# v1_2.net
KiCad netlist of a schematic drawn in EAGLE
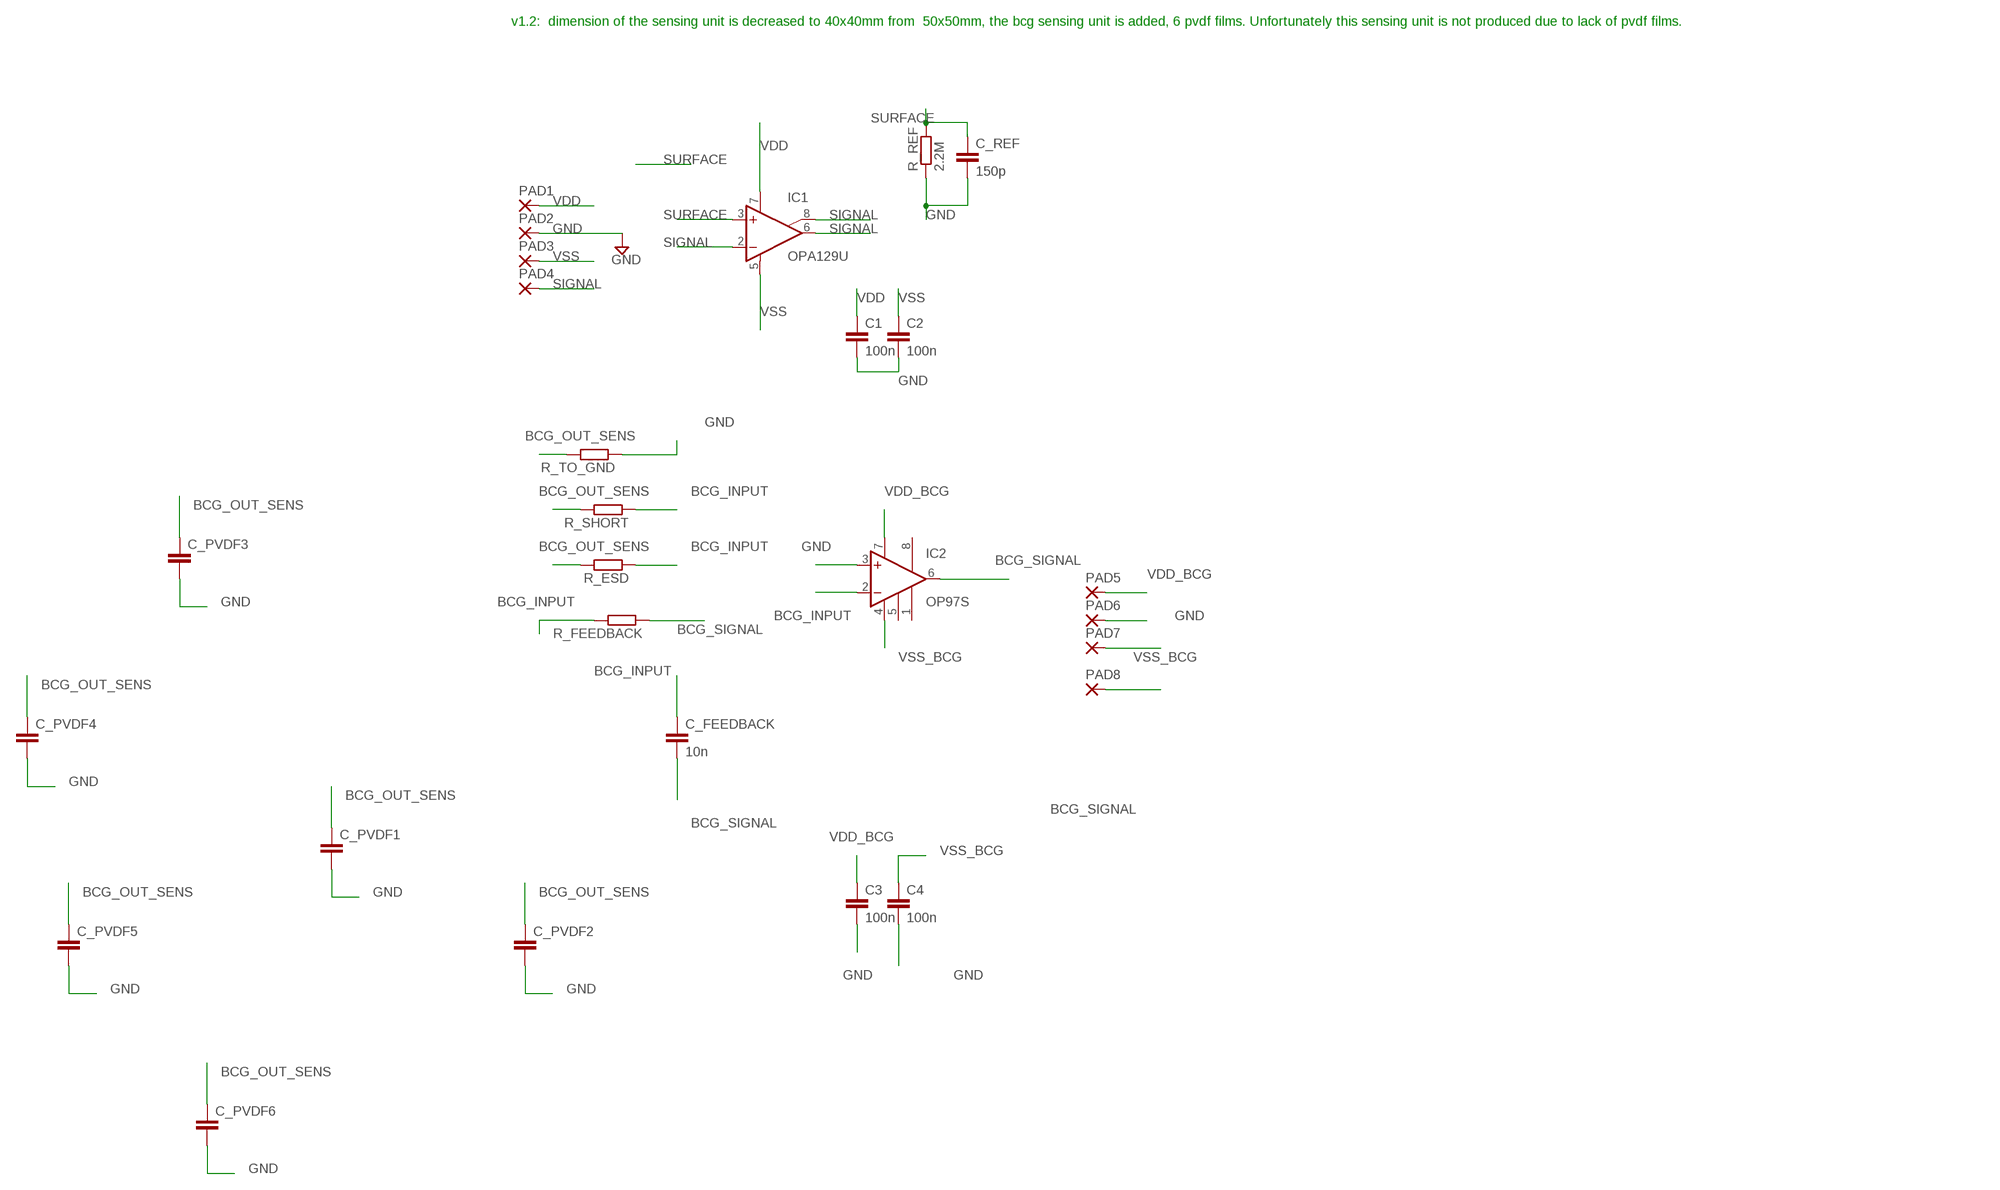
[diagram p0: schematic, sheet 1]

(export (version "E")
  (design (tool "Eeschema 10.0.6"))
  (components
    (comp (ref "C1")
      (value "100n")
      (footprint "eagle-import:C0805")
      (libsource (lib "eagle-import") (part "resistor_C-EUC0805"))
    )
    (comp (ref "C2")
      (value "100n")
      (footprint "eagle-import:C0805")
      (libsource (lib "eagle-import") (part "resistor_C-EUC0805"))
    )
    (comp (ref "C3")
      (value "100n")
      (footprint "eagle-import:C0805")
      (libsource (lib "eagle-import") (part "resistor_C-EUC0805"))
    )
    (comp (ref "C4")
      (value "100n")
      (footprint "eagle-import:C0805")
      (libsource (lib "eagle-import") (part "resistor_C-EUC0805"))
    )
    (comp (ref "C_FEEDBACK")
      (value "10n")
      (footprint "eagle-import:C0805")
      (libsource (lib "eagle-import") (part "C-EUC0805"))
    )
    (comp (ref "C_PVDF1")
      (value "C-EUC0805")
      (footprint "eagle-import:C0805")
      (libsource (lib "eagle-import") (part "C-EUC0805"))
    )
    (comp (ref "C_PVDF2")
      (value "C-EUC0805")
      (footprint "eagle-import:C0805")
      (libsource (lib "eagle-import") (part "C-EUC0805"))
    )
    (comp (ref "C_PVDF3")
      (value "C-EUC0805")
      (footprint "eagle-import:C0805")
      (libsource (lib "eagle-import") (part "C-EUC0805"))
    )
    (comp (ref "C_PVDF4")
      (value "C-EUC0805")
      (footprint "eagle-import:C0805")
      (libsource (lib "eagle-import") (part "C-EUC0805"))
    )
    (comp (ref "C_PVDF5")
      (value "C-EUC0805")
      (footprint "eagle-import:C0805")
      (libsource (lib "eagle-import") (part "C-EUC0805"))
    )
    (comp (ref "C_PVDF6")
      (value "C-EUC0805")
      (footprint "eagle-import:C0805")
      (libsource (lib "eagle-import") (part "C-EUC0805"))
    )
    (comp (ref "C_REF")
      (value "150p")
      (footprint "eagle-import:C0805")
      (libsource (lib "eagle-import") (part "resistor_C-EUC0805"))
    )
    (comp (ref "IC1")
      (value "OPA129U")
      (footprint "eagle-import:SO08")
      (fields (field (name "MF") "TEXAS INSTRUMENTS"))
      (libsource (lib "eagle-import") (part "OPA129U"))
    )
    (comp (ref "IC2")
      (value "OP97S")
      (footprint "eagle-import:SO08")
      (libsource (lib "eagle-import") (part "OP97S"))
    )
    (comp (ref "PAD1")
      (value "SMD5")
      (footprint "eagle-import:SMD2,54-5,08")
      (libsource (lib "eagle-import") (part "SMD5"))
    )
    (comp (ref "PAD2")
      (value "SMD5")
      (footprint "eagle-import:SMD2,54-5,08")
      (libsource (lib "eagle-import") (part "SMD5"))
    )
    (comp (ref "PAD3")
      (value "SMD5")
      (footprint "eagle-import:SMD2,54-5,08")
      (libsource (lib "eagle-import") (part "SMD5"))
    )
    (comp (ref "PAD4")
      (value "SMD5")
      (footprint "eagle-import:SMD2,54-5,08")
      (libsource (lib "eagle-import") (part "SMD5"))
    )
    (comp (ref "PAD5")
      (value "SMD5")
      (footprint "eagle-import:SMD2,54-5,08")
      (libsource (lib "eagle-import") (part "SMD5"))
    )
    (comp (ref "PAD6")
      (value "SMD5")
      (footprint "eagle-import:SMD2,54-5,08")
      (libsource (lib "eagle-import") (part "SMD5"))
    )
    (comp (ref "PAD7")
      (value "SMD5")
      (footprint "eagle-import:SMD2,54-5,08")
      (libsource (lib "eagle-import") (part "SMD5"))
    )
    (comp (ref "PAD8")
      (value "SMD5")
      (footprint "eagle-import:SMD2,54-5,08")
      (libsource (lib "eagle-import") (part "wirepad_412_SMD5"))
    )
    (comp (ref "R_ESD")
      (value "1M")
      (footprint "eagle-import:M0805")
      (libsource (lib "eagle-import") (part "rcl_334_R-EU_M0805"))
    )
    (comp (ref "R_FEEDBACK")
      (value "100M")
      (footprint "eagle-import:M0805")
      (libsource (lib "eagle-import") (part "rcl_334_R-EU_M0805"))
    )
    (comp (ref "R_REF")
      (value "2.2M")
      (footprint "eagle-import:M0805")
      (libsource (lib "eagle-import") (part "R-EU_M0805"))
    )
    (comp (ref "R_SHORT")
      (value "1M")
      (footprint "eagle-import:M0805")
      (libsource (lib "eagle-import") (part "rcl_334_R-EU_M0805"))
    )
    (comp (ref "R_TO_GND")
      (value "1M")
      (footprint "eagle-import:M0805")
      (libsource (lib "eagle-import") (part "rcl_334_R-EU_M0805"))
    )
  )
  (nets
    (net (code "1") (name "/BCG_INPUT") (class "Default")
      (node (ref "C_FEEDBACK") (pin "1") (pinfunction "1_1") (pintype "passive"))
      (node (ref "IC2") (pin "2") (pinfunction "-IN_2") (pintype "input"))
      (node (ref "R_ESD") (pin "1") (pinfunction "1_1") (pintype "passive"))
      (node (ref "R_FEEDBACK") (pin "2") (pinfunction "2_2") (pintype "passive"))
      (node (ref "R_SHORT") (pin "1") (pinfunction "1_1") (pintype "passive"))
    )
    (net (code "2") (name "/BCG_OUT_SENS") (class "Default")
      (node (ref "C_PVDF1") (pin "1") (pinfunction "1_1") (pintype "passive"))
      (node (ref "C_PVDF2") (pin "1") (pinfunction "1_1") (pintype "passive"))
      (node (ref "C_PVDF3") (pin "1") (pinfunction "1_1") (pintype "passive"))
      (node (ref "C_PVDF4") (pin "1") (pinfunction "1_1") (pintype "passive"))
      (node (ref "C_PVDF5") (pin "1") (pinfunction "1_1") (pintype "passive"))
      (node (ref "C_PVDF6") (pin "1") (pinfunction "1_1") (pintype "passive"))
      (node (ref "R_ESD") (pin "2") (pinfunction "2_2") (pintype "passive"))
      (node (ref "R_SHORT") (pin "2") (pinfunction "2_2") (pintype "passive"))
      (node (ref "R_TO_GND") (pin "2") (pinfunction "2_2") (pintype "passive"))
    )
    (net (code "3") (name "/BCG_SIGNAL") (class "Default")
      (node (ref "C_FEEDBACK") (pin "2") (pinfunction "2_2") (pintype "passive"))
      (node (ref "IC2") (pin "6") (pinfunction "OUT_6") (pintype "output"))
      (node (ref "PAD8") (pin "1") (pinfunction "P_1") (pintype "passive"))
      (node (ref "R_FEEDBACK") (pin "1") (pinfunction "1_1") (pintype "passive"))
    )
    (net (code "4") (name "/SIGNAL") (class "Default")
      (node (ref "IC1") (pin "2") (pinfunction "-IN_2") (pintype "input"))
      (node (ref "IC1") (pin "6") (pinfunction "OUT_6") (pintype "output"))
      (node (ref "IC1") (pin "8") (pinfunction "SUBS_8") (pintype "passive"))
      (node (ref "PAD4") (pin "1") (pinfunction "P_1") (pintype "passive"))
    )
    (net (code "5") (name "/SURFACE") (class "Default")
      (node (ref "C_REF") (pin "1") (pinfunction "1_1") (pintype "passive"))
      (node (ref "IC1") (pin "3") (pinfunction "+IN_3") (pintype "input"))
      (node (ref "R_REF") (pin "2") (pinfunction "2_2") (pintype "passive"))
    )
    (net (code "6") (name "/VDD") (class "Default")
      (node (ref "C1") (pin "1") (pinfunction "1_1") (pintype "passive"))
      (node (ref "IC1") (pin "7") (pinfunction "V+_7") (pintype "power_in"))
      (node (ref "PAD1") (pin "1") (pinfunction "P_1") (pintype "passive"))
    )
    (net (code "7") (name "/VDD_BCG") (class "Default")
      (node (ref "C3") (pin "1") (pinfunction "1_1") (pintype "passive"))
      (node (ref "IC2") (pin "7") (pinfunction "V+_7") (pintype "power_in"))
      (node (ref "PAD5") (pin "1") (pinfunction "P_1") (pintype "passive"))
    )
    (net (code "8") (name "/VSS") (class "Default")
      (node (ref "C2") (pin "1") (pinfunction "1_1") (pintype "passive"))
      (node (ref "IC1") (pin "5") (pinfunction "V-_5") (pintype "power_in"))
      (node (ref "PAD3") (pin "1") (pinfunction "P_1") (pintype "passive"))
    )
    (net (code "9") (name "/VSS_BCG") (class "Default")
      (node (ref "C4") (pin "1") (pinfunction "1_1") (pintype "passive"))
      (node (ref "IC2") (pin "4") (pinfunction "V-_4") (pintype "power_in"))
      (node (ref "PAD7") (pin "1") (pinfunction "P_1") (pintype "passive"))
    )
    (net (code "10") (name "GND") (class "Default")
      (node (ref "C1") (pin "2") (pinfunction "2_2") (pintype "passive"))
      (node (ref "C2") (pin "2") (pinfunction "2_2") (pintype "passive"))
      (node (ref "C3") (pin "2") (pinfunction "2_2") (pintype "passive"))
      (node (ref "C4") (pin "2") (pinfunction "2_2") (pintype "passive"))
      (node (ref "C_PVDF1") (pin "2") (pinfunction "2_2") (pintype "passive"))
      (node (ref "C_PVDF2") (pin "2") (pinfunction "2_2") (pintype "passive"))
      (node (ref "C_PVDF3") (pin "2") (pinfunction "2_2") (pintype "passive"))
      (node (ref "C_PVDF4") (pin "2") (pinfunction "2_2") (pintype "passive"))
      (node (ref "C_PVDF5") (pin "2") (pinfunction "2_2") (pintype "passive"))
      (node (ref "C_PVDF6") (pin "2") (pinfunction "2_2") (pintype "passive"))
      (node (ref "C_REF") (pin "2") (pinfunction "2_2") (pintype "passive"))
      (node (ref "IC2") (pin "3") (pinfunction "+IN_3") (pintype "input"))
      (node (ref "PAD2") (pin "1") (pinfunction "P_1") (pintype "passive"))
      (node (ref "PAD6") (pin "1") (pinfunction "P_1") (pintype "passive"))
      (node (ref "R_REF") (pin "1") (pinfunction "1_1") (pintype "passive"))
      (node (ref "R_TO_GND") (pin "1") (pinfunction "1_1") (pintype "passive"))
    )
    (net (code "11") (name "unconnected-(IC2-BAL1-Pad1)") (class "Default")
      (node (ref "IC2") (pin "1") (pinfunction "BAL1_1") (pintype "passive"))
    )
    (net (code "12") (name "unconnected-(IC2-BAL2-Pad8)") (class "Default")
      (node (ref "IC2") (pin "8") (pinfunction "BAL2_8") (pintype "passive"))
    )
    (net (code "13") (name "unconnected-(IC2-COMP-Pad5)") (class "Default")
      (node (ref "IC2") (pin "5") (pinfunction "COMP_5") (pintype "passive"))
    )
  )
)
